# device.net
KiCad netlist of a schematic drawn in EAGLE
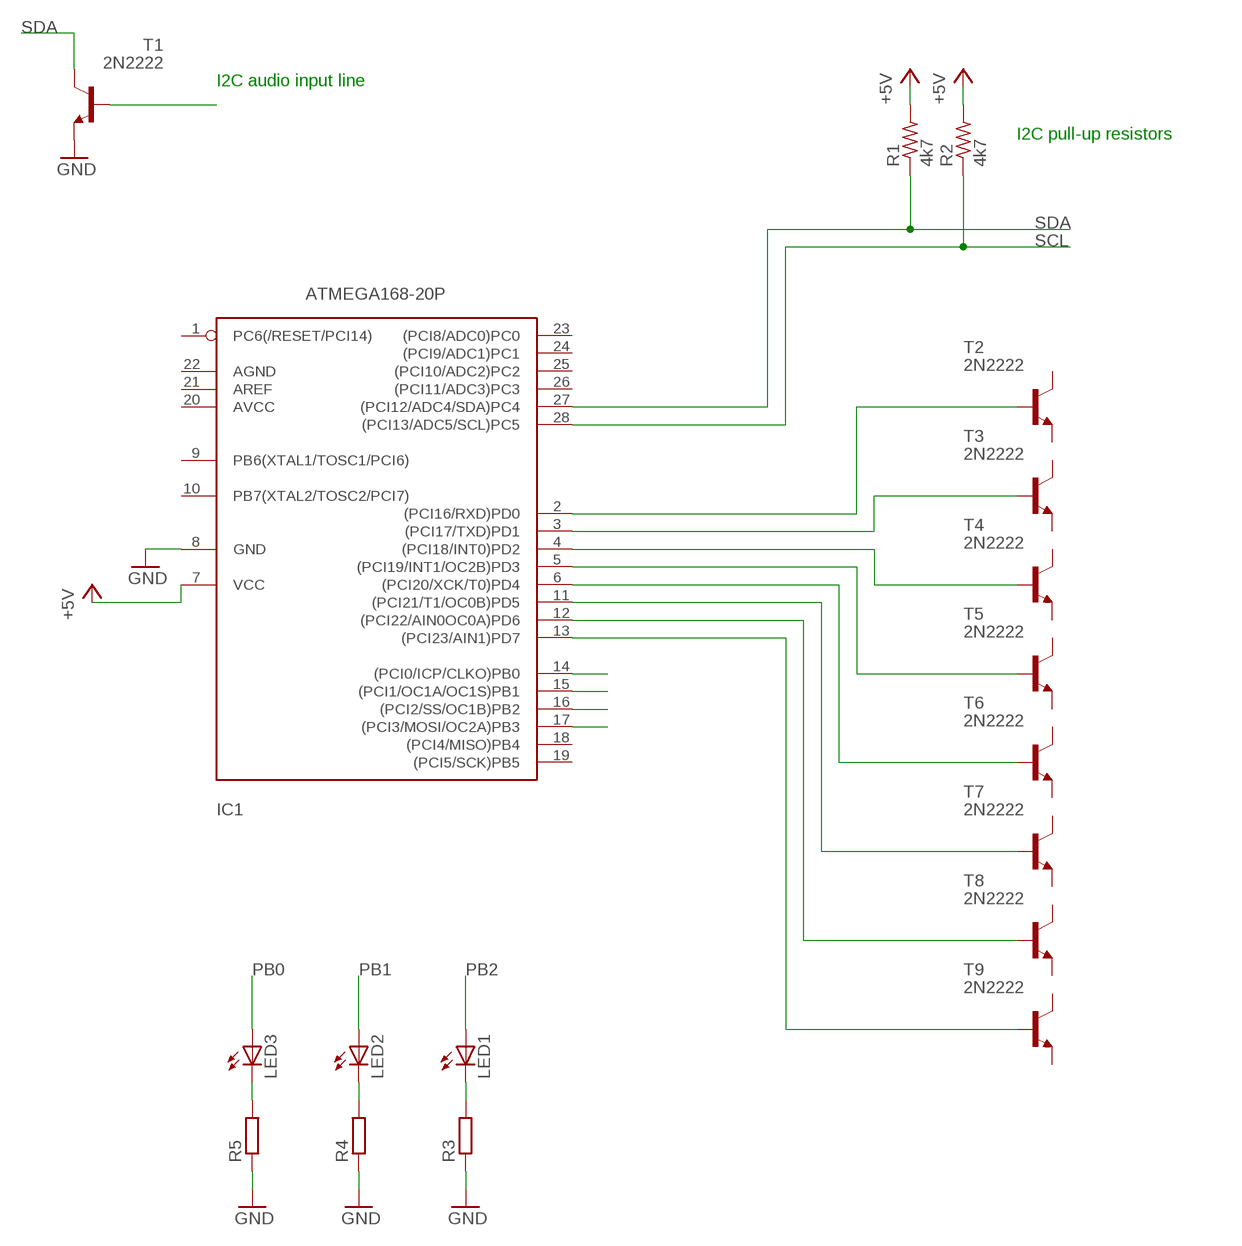
[diagram p0: schematic, sheet 1]

(export (version "E")
  (design (tool "Eeschema 10.0.6"))
  (components
    (comp (ref "IC1")
      (value "ATMEGA168-20P")
      (footprint "eagle-import:DIL28-3")
      (libsource (lib "eagle-import") (part "ATMEGA168P-20"))
    )
    (comp (ref "LED1")
      (value "LED_ELD260")
      (footprint "eagle-import:LED_LD260")
      (libsource (lib "eagle-import") (part "LED_ELD260"))
    )
    (comp (ref "LED2")
      (value "LED_ELD260")
      (footprint "eagle-import:LED_LD260")
      (libsource (lib "eagle-import") (part "LED_ELD260"))
    )
    (comp (ref "LED3")
      (value "LED_ELD260")
      (footprint "eagle-import:LED_LD260")
      (libsource (lib "eagle-import") (part "LED_ELD260"))
    )
    (comp (ref "R1")
      (value "4k7")
      (footprint "eagle-import:0204V")
      (libsource (lib "eagle-import") (part "R-US_0204/2V"))
    )
    (comp (ref "R2")
      (value "4k7")
      (footprint "eagle-import:0204V")
      (libsource (lib "eagle-import") (part "R-US_0204/2V"))
    )
    (comp (ref "R3")
      (value "R-EU_0204/5")
      (footprint "eagle-import:0204_5")
      (libsource (lib "eagle-import") (part "R-EU_0204/5"))
    )
    (comp (ref "R4")
      (value "R-EU_0204/5")
      (footprint "eagle-import:0204_5")
      (libsource (lib "eagle-import") (part "R-EU_0204/5"))
    )
    (comp (ref "R5")
      (value "R-EU_0204/5")
      (footprint "eagle-import:0204_5")
      (libsource (lib "eagle-import") (part "R-EU_0204/5"))
    )
    (comp (ref "T1")
      (value "2N2222")
      (footprint "eagle-import:TO92-EBC-OVAL")
      (libsource (lib "eagle-import") (part "2N2222"))
    )
    (comp (ref "T2")
      (value "2N2222")
      (footprint "eagle-import:TO92-EBC-OVAL")
      (libsource (lib "eagle-import") (part "2N2222"))
    )
    (comp (ref "T3")
      (value "2N2222")
      (footprint "eagle-import:TO92-EBC-OVAL")
      (libsource (lib "eagle-import") (part "2N2222"))
    )
    (comp (ref "T4")
      (value "2N2222")
      (footprint "eagle-import:TO92-EBC-OVAL")
      (libsource (lib "eagle-import") (part "2N2222"))
    )
    (comp (ref "T5")
      (value "2N2222")
      (footprint "eagle-import:TO92-EBC-OVAL")
      (libsource (lib "eagle-import") (part "2N2222"))
    )
    (comp (ref "T6")
      (value "2N2222")
      (footprint "eagle-import:TO92-EBC-OVAL")
      (libsource (lib "eagle-import") (part "2N2222"))
    )
    (comp (ref "T7")
      (value "2N2222")
      (footprint "eagle-import:TO92-EBC-OVAL")
      (libsource (lib "eagle-import") (part "2N2222"))
    )
    (comp (ref "T8")
      (value "2N2222")
      (footprint "eagle-import:TO92-EBC-OVAL")
      (libsource (lib "eagle-import") (part "2N2222"))
    )
    (comp (ref "T9")
      (value "2N2222")
      (footprint "eagle-import:TO92-EBC-OVAL")
      (libsource (lib "eagle-import") (part "2N2222"))
    )
  )
  (nets
    (net (code "1") (name "+5V") (class "Default")
      (node (ref "IC1") (pin "7") (pinfunction "VCC_7") (pintype "bidirectional"))
      (node (ref "R1") (pin "2") (pinfunction "2_2") (pintype "passive"))
      (node (ref "R2") (pin "2") (pinfunction "2_2") (pintype "passive"))
    )
    (net (code "2") (name "/PB0") (class "Default")
      (node (ref "IC1") (pin "14") (pinfunction "(PCI0/ICP/CLKO)PB0_14") (pintype "bidirectional"))
      (node (ref "LED3") (pin "A") (pinfunction "A_A") (pintype "passive"))
    )
    (net (code "3") (name "/PB1") (class "Default")
      (node (ref "IC1") (pin "15") (pinfunction "(PCI1/OC1A/OC1S)PB1_15") (pintype "bidirectional"))
      (node (ref "LED2") (pin "A") (pinfunction "A_A") (pintype "passive"))
    )
    (net (code "4") (name "/PB2") (class "Default")
      (node (ref "IC1") (pin "16") (pinfunction "(PCI2/SS/OC1B)PB2_16") (pintype "bidirectional"))
      (node (ref "LED1") (pin "A") (pinfunction "A_A") (pintype "passive"))
    )
    (net (code "5") (name "/SCL") (class "Default")
      (node (ref "IC1") (pin "28") (pinfunction "(PCI13/ADC5/SCL)PC5_28") (pintype "bidirectional"))
      (node (ref "R2") (pin "1") (pinfunction "1_1") (pintype "passive"))
    )
    (net (code "6") (name "/SDA") (class "Default")
      (node (ref "IC1") (pin "27") (pinfunction "(PCI12/ADC4/SDA)PC4_27") (pintype "bidirectional"))
      (node (ref "R1") (pin "1") (pinfunction "1_1") (pintype "passive"))
      (node (ref "T1") (pin "C") (pinfunction "C_C") (pintype "passive"))
    )
    (net (code "7") (name "GND") (class "Default")
      (node (ref "IC1") (pin "8") (pinfunction "GND_8") (pintype "bidirectional"))
      (node (ref "R3") (pin "1") (pinfunction "1_1") (pintype "passive"))
      (node (ref "R4") (pin "1") (pinfunction "1_1") (pintype "passive"))
      (node (ref "R5") (pin "1") (pinfunction "1_1") (pintype "passive"))
      (node (ref "T1") (pin "E") (pinfunction "E_E") (pintype "passive"))
    )
    (net (code "8") (name "Net-(IC1-(PCI16{slash}RXD)PD0)") (class "Default")
      (node (ref "IC1") (pin "2") (pinfunction "(PCI16/RXD)PD0_2") (pintype "bidirectional"))
      (node (ref "T2") (pin "B") (pinfunction "B_B") (pintype "passive"))
    )
    (net (code "9") (name "Net-(IC1-(PCI17{slash}TXD)PD1)") (class "Default")
      (node (ref "IC1") (pin "3") (pinfunction "(PCI17/TXD)PD1_3") (pintype "bidirectional"))
      (node (ref "T3") (pin "B") (pinfunction "B_B") (pintype "passive"))
    )
    (net (code "10") (name "Net-(IC1-(PCI18{slash}INT0)PD2)") (class "Default")
      (node (ref "IC1") (pin "4") (pinfunction "(PCI18/INT0)PD2_4") (pintype "bidirectional"))
      (node (ref "T4") (pin "B") (pinfunction "B_B") (pintype "passive"))
    )
    (net (code "11") (name "Net-(IC1-(PCI19{slash}INT1{slash}OC2B)PD3)") (class "Default")
      (node (ref "IC1") (pin "5") (pinfunction "(PCI19/INT1/OC2B)PD3_5") (pintype "bidirectional"))
      (node (ref "T5") (pin "B") (pinfunction "B_B") (pintype "passive"))
    )
    (net (code "12") (name "Net-(IC1-(PCI20{slash}XCK{slash}T0)PD4)") (class "Default")
      (node (ref "IC1") (pin "6") (pinfunction "(PCI20/XCK/T0)PD4_6") (pintype "bidirectional"))
      (node (ref "T6") (pin "B") (pinfunction "B_B") (pintype "passive"))
    )
    (net (code "13") (name "Net-(IC1-(PCI21{slash}T1{slash}OC0B)PD5)") (class "Default")
      (node (ref "IC1") (pin "11") (pinfunction "(PCI21/T1/OC0B)PD5_11") (pintype "bidirectional"))
      (node (ref "T7") (pin "B") (pinfunction "B_B") (pintype "passive"))
    )
    (net (code "14") (name "Net-(IC1-(PCI22{slash}AIN0OC0A)PD6)") (class "Default")
      (node (ref "IC1") (pin "12") (pinfunction "(PCI22/AIN0OC0A)PD6_12") (pintype "bidirectional"))
      (node (ref "T8") (pin "B") (pinfunction "B_B") (pintype "passive"))
    )
    (net (code "15") (name "Net-(IC1-(PCI23{slash}AIN1)PD7)") (class "Default")
      (node (ref "IC1") (pin "13") (pinfunction "(PCI23/AIN1)PD7_13") (pintype "bidirectional"))
      (node (ref "T9") (pin "B") (pinfunction "B_B") (pintype "passive"))
    )
    (net (code "16") (name "Net-(LED1-C)") (class "Default")
      (node (ref "LED1") (pin "K") (pinfunction "C_K") (pintype "passive"))
      (node (ref "R3") (pin "2") (pinfunction "2_2") (pintype "passive"))
    )
    (net (code "17") (name "Net-(LED2-C)") (class "Default")
      (node (ref "LED2") (pin "K") (pinfunction "C_K") (pintype "passive"))
      (node (ref "R4") (pin "2") (pinfunction "2_2") (pintype "passive"))
    )
    (net (code "18") (name "Net-(LED3-C)") (class "Default")
      (node (ref "LED3") (pin "K") (pinfunction "C_K") (pintype "passive"))
      (node (ref "R5") (pin "2") (pinfunction "2_2") (pintype "passive"))
    )
    (net (code "19") (name "unconnected-(IC1-(PCI3{slash}MOSI{slash}OC2A)PB3-Pad17)") (class "Default")
      (node (ref "IC1") (pin "17") (pinfunction "(PCI3/MOSI/OC2A)PB3_17") (pintype "bidirectional"))
    )
    (net (code "20") (name "unconnected-(IC1-(PCI4{slash}MISO)PB4-Pad18)") (class "Default")
      (node (ref "IC1") (pin "18") (pinfunction "(PCI4/MISO)PB4_18") (pintype "bidirectional"))
    )
    (net (code "21") (name "unconnected-(IC1-(PCI5{slash}SCK)PB5-Pad19)") (class "Default")
      (node (ref "IC1") (pin "19") (pinfunction "(PCI5/SCK)PB5_19") (pintype "bidirectional"))
    )
    (net (code "22") (name "unconnected-(IC1-(PCI8{slash}ADC0)PC0-Pad23)") (class "Default")
      (node (ref "IC1") (pin "23") (pinfunction "(PCI8/ADC0)PC0_23") (pintype "bidirectional"))
    )
    (net (code "23") (name "unconnected-(IC1-(PCI9{slash}ADC1)PC1-Pad24)") (class "Default")
      (node (ref "IC1") (pin "24") (pinfunction "(PCI9/ADC1)PC1_24") (pintype "bidirectional"))
    )
    (net (code "24") (name "unconnected-(IC1-(PCI10{slash}ADC2)PC2-Pad25)") (class "Default")
      (node (ref "IC1") (pin "25") (pinfunction "(PCI10/ADC2)PC2_25") (pintype "bidirectional"))
    )
    (net (code "25") (name "unconnected-(IC1-(PCI11{slash}ADC3)PC3-Pad26)") (class "Default")
      (node (ref "IC1") (pin "26") (pinfunction "(PCI11/ADC3)PC3_26") (pintype "bidirectional"))
    )
    (net (code "26") (name "unconnected-(IC1-AGND-Pad22)") (class "Default")
      (node (ref "IC1") (pin "22") (pinfunction "AGND_22") (pintype "bidirectional"))
    )
    (net (code "27") (name "unconnected-(IC1-AREF-Pad21)") (class "Default")
      (node (ref "IC1") (pin "21") (pinfunction "AREF_21") (pintype "bidirectional"))
    )
    (net (code "28") (name "unconnected-(IC1-AVCC-Pad20)") (class "Default")
      (node (ref "IC1") (pin "20") (pinfunction "AVCC_20") (pintype "bidirectional"))
    )
    (net (code "29") (name "unconnected-(IC1-PB6(XTAL1{slash}TOSC1{slash}PCI6)-Pad9)") (class "Default")
      (node (ref "IC1") (pin "9") (pinfunction "PB6(XTAL1/TOSC1/PCI6)_9") (pintype "bidirectional"))
    )
    (net (code "30") (name "unconnected-(IC1-PB7(XTAL2{slash}TOSC2{slash}PCI7)-Pad10)") (class "Default")
      (node (ref "IC1") (pin "10") (pinfunction "PB7(XTAL2/TOSC2/PCI7)_10") (pintype "bidirectional"))
    )
    (net (code "31") (name "unconnected-(IC1-PC6({slash}RESET{slash}PCI14)-Pad1)") (class "Default")
      (node (ref "IC1") (pin "1") (pinfunction "PC6(/RESET/PCI14)_1") (pintype "bidirectional"))
    )
    (net (code "32") (name "unconnected-(T1-PadB)") (class "Default")
      (node (ref "T1") (pin "B") (pinfunction "B_B") (pintype "passive"))
    )
    (net (code "33") (name "unconnected-(T2-PadC)") (class "Default")
      (node (ref "T2") (pin "C") (pinfunction "C_C") (pintype "passive"))
    )
    (net (code "34") (name "unconnected-(T2-PadE)") (class "Default")
      (node (ref "T2") (pin "E") (pinfunction "E_E") (pintype "passive"))
    )
    (net (code "35") (name "unconnected-(T3-PadC)") (class "Default")
      (node (ref "T3") (pin "C") (pinfunction "C_C") (pintype "passive"))
    )
    (net (code "36") (name "unconnected-(T3-PadE)") (class "Default")
      (node (ref "T3") (pin "E") (pinfunction "E_E") (pintype "passive"))
    )
    (net (code "37") (name "unconnected-(T4-PadC)") (class "Default")
      (node (ref "T4") (pin "C") (pinfunction "C_C") (pintype "passive"))
    )
    (net (code "38") (name "unconnected-(T4-PadE)") (class "Default")
      (node (ref "T4") (pin "E") (pinfunction "E_E") (pintype "passive"))
    )
    (net (code "39") (name "unconnected-(T5-PadC)") (class "Default")
      (node (ref "T5") (pin "C") (pinfunction "C_C") (pintype "passive"))
    )
    (net (code "40") (name "unconnected-(T5-PadE)") (class "Default")
      (node (ref "T5") (pin "E") (pinfunction "E_E") (pintype "passive"))
    )
    (net (code "41") (name "unconnected-(T6-PadC)") (class "Default")
      (node (ref "T6") (pin "C") (pinfunction "C_C") (pintype "passive"))
    )
    (net (code "42") (name "unconnected-(T6-PadE)") (class "Default")
      (node (ref "T6") (pin "E") (pinfunction "E_E") (pintype "passive"))
    )
    (net (code "43") (name "unconnected-(T7-PadC)") (class "Default")
      (node (ref "T7") (pin "C") (pinfunction "C_C") (pintype "passive"))
    )
    (net (code "44") (name "unconnected-(T7-PadE)") (class "Default")
      (node (ref "T7") (pin "E") (pinfunction "E_E") (pintype "passive"))
    )
    (net (code "45") (name "unconnected-(T8-PadC)") (class "Default")
      (node (ref "T8") (pin "C") (pinfunction "C_C") (pintype "passive"))
    )
    (net (code "46") (name "unconnected-(T8-PadE)") (class "Default")
      (node (ref "T8") (pin "E") (pinfunction "E_E") (pintype "passive"))
    )
    (net (code "47") (name "unconnected-(T9-PadC)") (class "Default")
      (node (ref "T9") (pin "C") (pinfunction "C_C") (pintype "passive"))
    )
    (net (code "48") (name "unconnected-(T9-PadE)") (class "Default")
      (node (ref "T9") (pin "E") (pinfunction "E_E") (pintype "passive"))
    )
  )
)
